# PowerSupply.net
KiCad netlist of a schematic drawn in Altium Designer
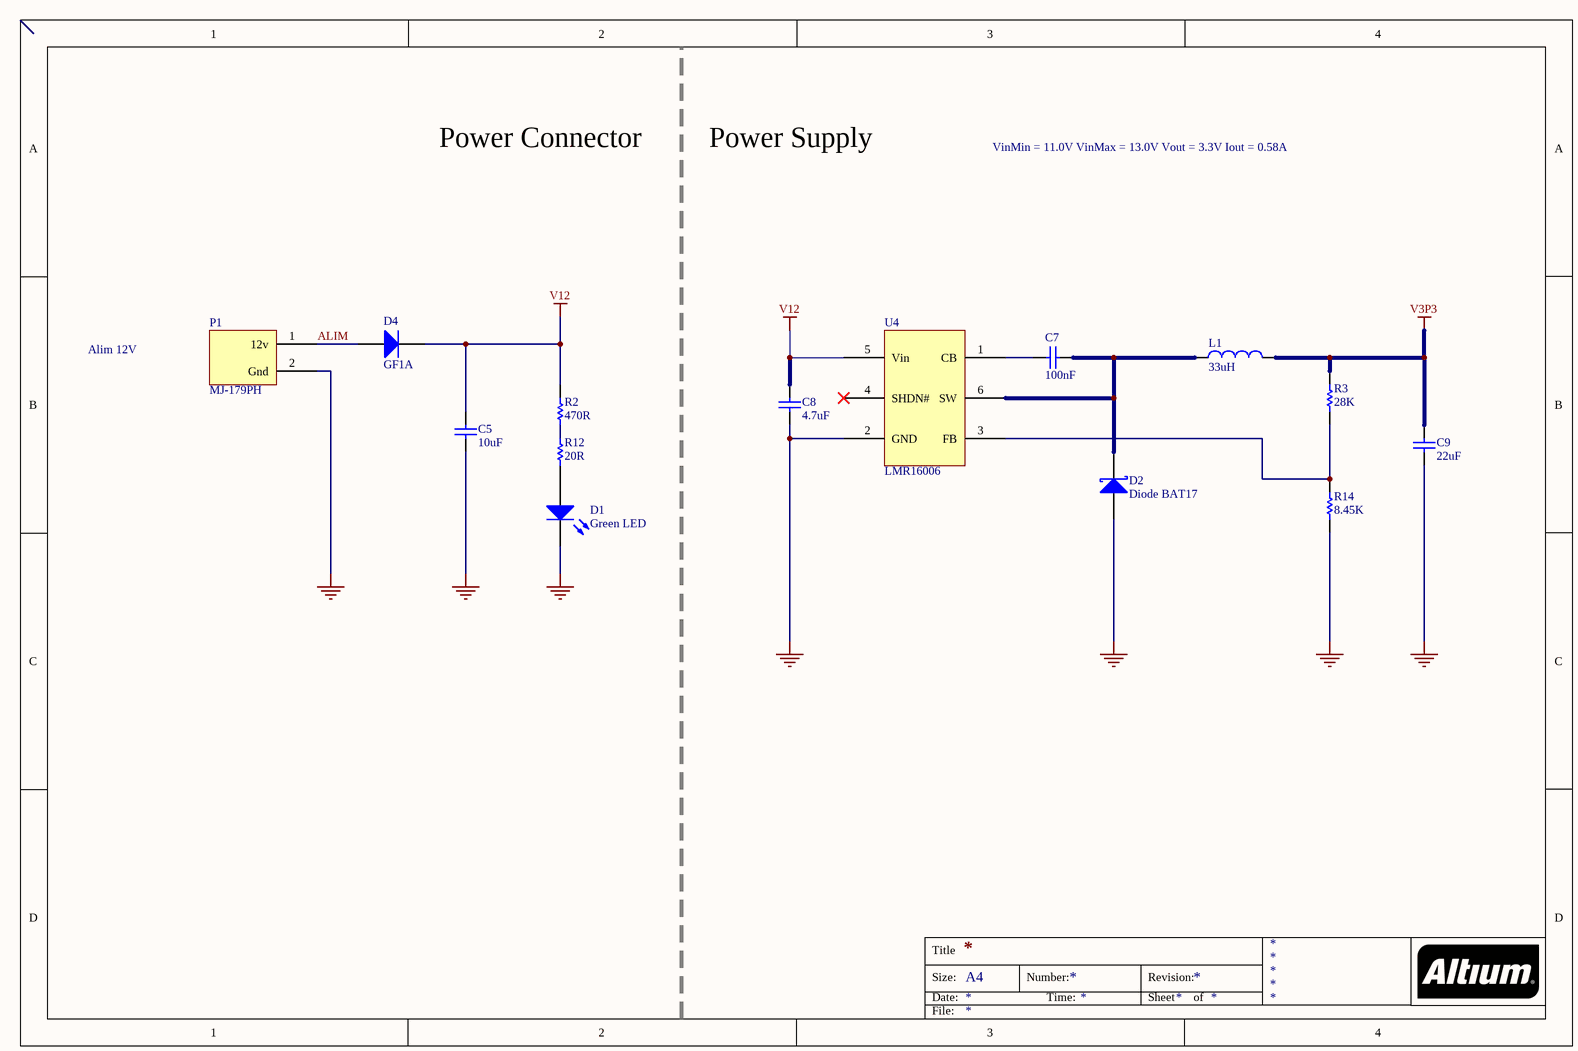
[diagram p0: PowerSupply.SchDoc]

(export (version "E")
  (design (tool "Eeschema 10.0.6"))
  (components
    (comp (ref "C5")
      (value "10uF")
      (footprint "CAP 0603")
      (description "Capacitor")
      (fields (field (name "PUBLISHER") "Altium Limited"))
      (libsource (lib "Miscellaneous Devices") (part "Cap"))
    )
    (comp (ref "C7")
      (value "100nF")
      (footprint "CAP 0603")
      (description "Capacitor")
      (fields (field (name "PUBLISHER") "Altium Limited"))
      (libsource (lib "Miscellaneous Devices") (part "Cap"))
    )
    (comp (ref "C8")
      (value "4.7uF")
      (footprint "CAP 0603")
      (description "Capacitor")
      (fields (field (name "PUBLISHER") "Altium Limited"))
      (libsource (lib "Miscellaneous Devices") (part "Cap"))
    )
    (comp (ref "C9")
      (value "22uF")
      (footprint "CAP 0603")
      (description "Capacitor")
      (fields (field (name "PUBLISHER") "Altium Limited"))
      (libsource (lib "Miscellaneous Devices") (part "Cap"))
    )
    (comp (ref "D1")
      (value "Green LED")
      (footprint "LED 2012")
      (description "Typical INFRARED GaAs LED")
      (fields (field (name "PUBLISHER") "Altium Limited"))
      (libsource (lib "Miscellaneous Devices") (part "LED2"))
    )
    (comp (ref "D2")
      (value "Diode BAT17")
      (footprint "SOD-123F 12 mm")
      (description "Silicon RF Schottky Diode for Mixer Applications in the VHF/UHF Range")
      (fields (field (name "PUBLISHER") "Altium Limited"))
      (libsource (lib "Miscellaneous Devices") (part "Diode BAT17"))
    )
    (comp (ref "D4")
      (value "GF1A")
      (footprint "SMA/DO-214AC_21")
      (description "Default Diode")
      (fields (field (name "PUBLISHER") "Altium Limited"))
      (libsource (lib "Miscellaneous Devices") (part "Diode"))
    )
    (comp (ref "L1")
      (value "33uH")
      (footprint "IND")
      (description "Inductor")
      (fields (field (name "PUBLISHER") "Altium Limited"))
      (libsource (lib "Miscellaneous Devices") (part "Inductor"))
    )
    (comp (ref "P1")
      (value "MJ-179PH")
      (footprint "Card_reader:DC Jack")
      (description "Connecteurs DC Jacks")
      (libsource (lib "Schlib1") (part "MJ-179PH"))
    )
    (comp (ref "R2")
      (value "470R")
      (footprint "RES 0603")
      (description "Resistor")
      (fields (field (name "PUBLISHER") "Altium Limited"))
      (libsource (lib "Miscellaneous Devices") (part "Res1"))
    )
    (comp (ref "R3")
      (value "28K")
      (footprint "RES 0603")
      (description "Resistor")
      (fields (field (name "PUBLISHER") "Altium Limited"))
      (libsource (lib "Miscellaneous Devices") (part "Res1"))
    )
    (comp (ref "R12")
      (value "20R")
      (footprint "RES 0603")
      (description "Resistor")
      (fields (field (name "PUBLISHER") "Altium Limited"))
      (libsource (lib "Miscellaneous Devices") (part "Res1"))
    )
    (comp (ref "R14")
      (value "8.45K")
      (footprint "RES 0603")
      (description "Resistor")
      (fields (field (name "PUBLISHER") "Altium Limited"))
      (libsource (lib "Miscellaneous Devices") (part "Res1"))
    )
    (comp (ref "U4")
      (value "LMR16006")
      (footprint "SOT (6)")
      (description "Régulateurs à découpage DC/DC ajustables")
      (libsource (lib "Card_reader") (part "LMR16006"))
    )
  )
  (nets
    (net (code "1") (name "/ALIM") (class "Default")
      (node (ref "D4") (pin "1") (pinfunction "A_1") (pintype "passive"))
      (node (ref "P1") (pin "1") (pinfunction "12v_1") (pintype "passive"))
    )
    (net (code "2") (name "GND") (class "Default")
      (node (ref "C5") (pin "1") (pinfunction "1_1") (pintype "passive"))
      (node (ref "C8") (pin "2") (pinfunction "2_2") (pintype "passive"))
      (node (ref "C9") (pin "2") (pinfunction "2_2") (pintype "passive"))
      (node (ref "D1") (pin "2") (pinfunction "K_2") (pintype "passive"))
      (node (ref "D2") (pin "1") (pinfunction "A_1") (pintype "passive"))
      (node (ref "P1") (pin "2") (pinfunction "Gnd_2") (pintype "passive"))
      (node (ref "R14") (pin "1") (pinfunction "1_1") (pintype "passive"))
      (node (ref "U4") (pin "2") (pinfunction "GND_2") (pintype "passive"))
    )
    (net (code "3") (name "Net-(D1-A)") (class "Default")
      (node (ref "D1") (pin "1") (pinfunction "A_1") (pintype "passive"))
      (node (ref "R12") (pin "1") (pinfunction "1_1") (pintype "passive"))
    )
    (net (code "4") (name "Net-(D2-K)") (class "Default")
      (node (ref "C7") (pin "2") (pinfunction "2_2") (pintype "passive"))
      (node (ref "D2") (pin "3") (pinfunction "K_3") (pintype "passive"))
      (node (ref "L1") (pin "1") (pinfunction "1_1") (pintype "passive"))
      (node (ref "U4") (pin "6") (pinfunction "SW_6") (pintype "passive"))
    )
    (net (code "5") (name "Net-(R12-Pad2)") (class "Default")
      (node (ref "R12") (pin "2") (pinfunction "2_2") (pintype "passive"))
      (node (ref "R2") (pin "1") (pinfunction "1_1") (pintype "passive"))
    )
    (net (code "6") (name "Net-(U4-CB)") (class "Default")
      (node (ref "C7") (pin "1") (pinfunction "1_1") (pintype "passive"))
      (node (ref "U4") (pin "1") (pinfunction "CB_1") (pintype "passive"))
    )
    (net (code "7") (name "Net-(U4-FB)") (class "Default")
      (node (ref "R14") (pin "2") (pinfunction "2_2") (pintype "passive"))
      (node (ref "R3") (pin "1") (pinfunction "1_1") (pintype "passive"))
      (node (ref "U4") (pin "3") (pinfunction "FB_3") (pintype "passive"))
    )
    (net (code "8") (name "V3P3") (class "Default")
      (node (ref "C9") (pin "1") (pinfunction "1_1") (pintype "passive"))
      (node (ref "L1") (pin "2") (pinfunction "2_2") (pintype "passive"))
      (node (ref "R3") (pin "2") (pinfunction "2_2") (pintype "passive"))
    )
    (net (code "9") (name "V12") (class "Default")
      (node (ref "C5") (pin "2") (pinfunction "2_2") (pintype "passive"))
      (node (ref "C8") (pin "1") (pinfunction "1_1") (pintype "passive"))
      (node (ref "D4") (pin "2") (pinfunction "K_2") (pintype "passive"))
      (node (ref "R2") (pin "2") (pinfunction "2_2") (pintype "passive"))
      (node (ref "U4") (pin "5") (pinfunction "Vin_5") (pintype "passive"))
    )
    (net (code "10") (name "unconnected-(U4-SHDN#-Pad4)") (class "Default")
      (node (ref "U4") (pin "4") (pinfunction "SHDN#_4") (pintype "passive+no_connect"))
    )
  )
)
